# LPC1768_3.net
KiCad netlist of a schematic drawn in Altium Designer
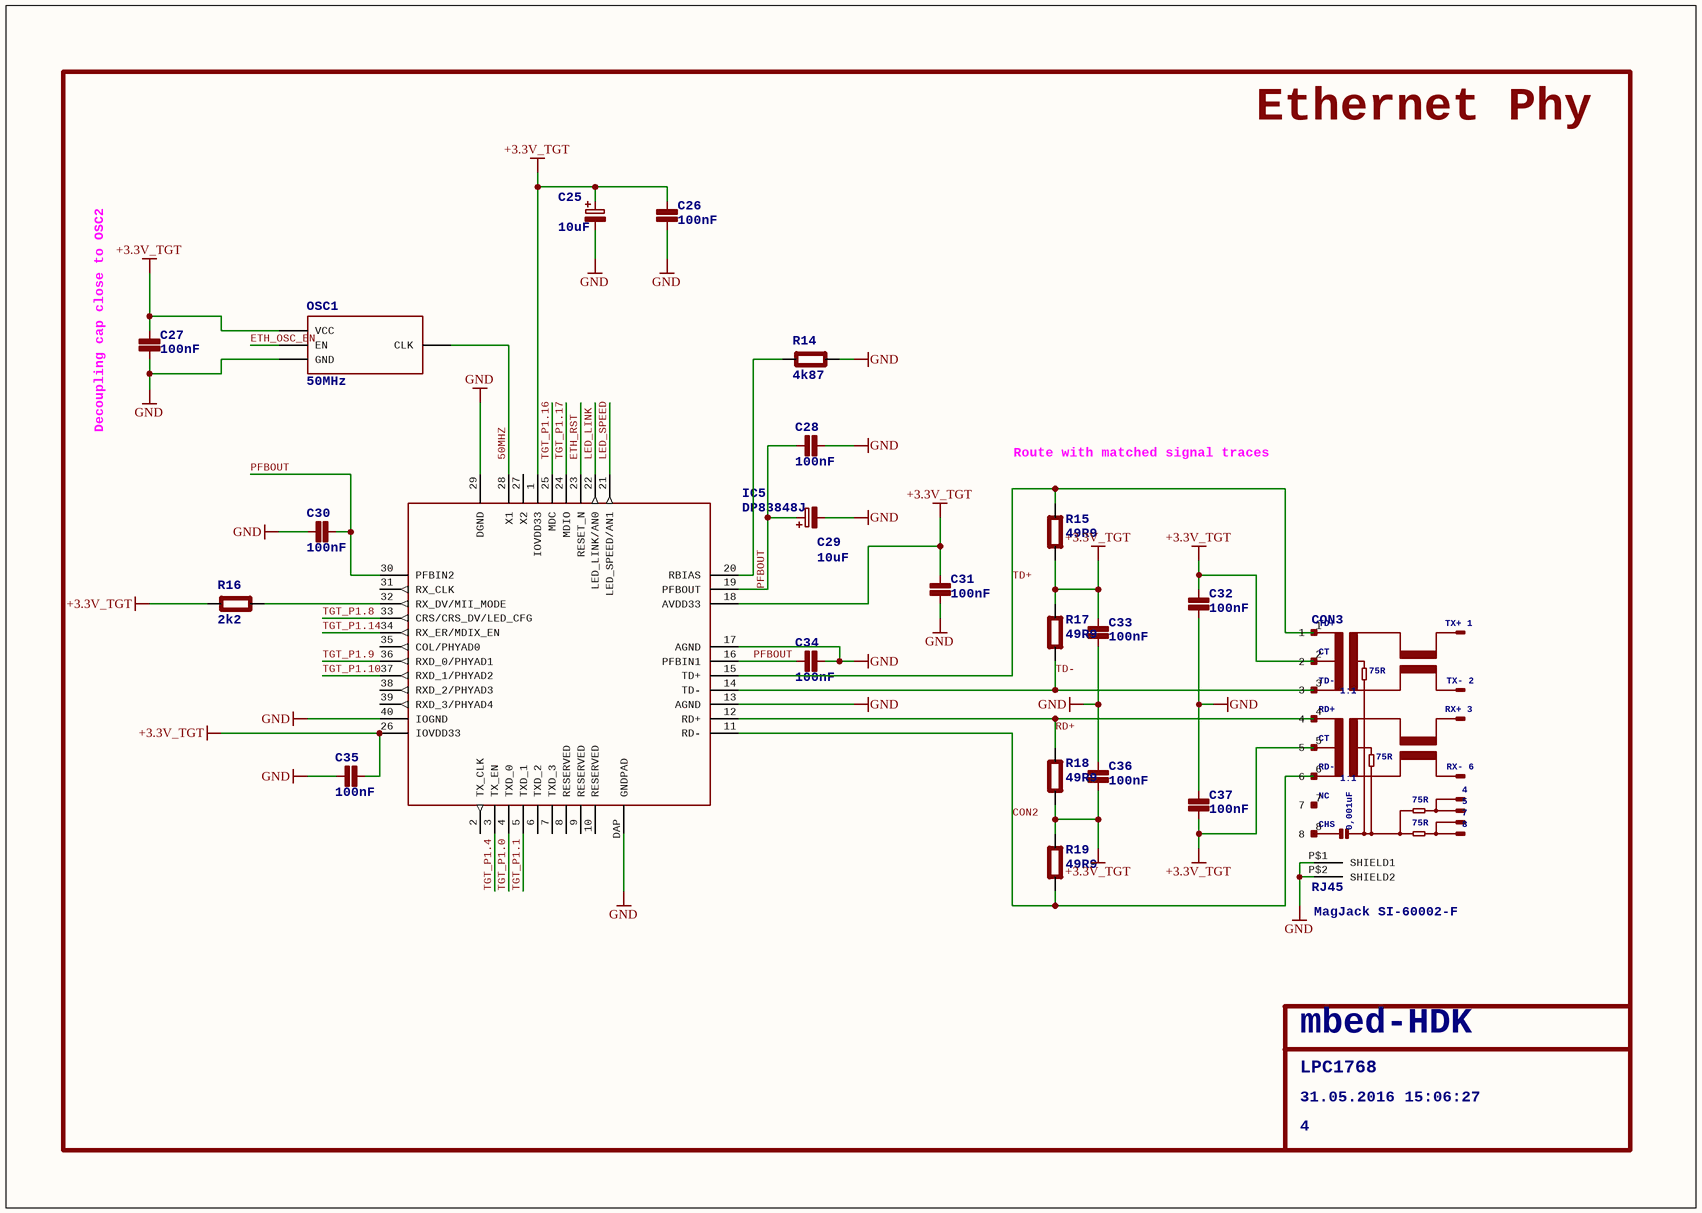
[diagram p0: LPC1768_3.SchDoc]

(export (version "E")
  (design (tool "Eeschema 10.0.6"))
  (components
    (comp (ref "C25") (value "10uF") (footprint "CASE-B") (libsource (lib "mbed-HDK") (part "C-POLB")))
    (comp (ref "C26") (value "100nF") (footprint "0603") (libsource (lib "mbed-HDK") (part "C0603")))
    (comp (ref "C27") (value "100nF") (footprint "0603") (libsource (lib "mbed-HDK") (part "C0603")))
    (comp (ref "C28") (value "100nF") (footprint "0603") (libsource (lib "") (part "C0603_1")))
    (comp (ref "C29") (value "10uF") (footprint "CASE-B") (libsource (lib "") (part "C-POLB_1")))
    (comp (ref "C30") (value "100nF") (footprint "0603") (libsource (lib "") (part "C0603_2")))
    (comp (ref "C31") (value "100nF") (footprint "0603") (libsource (lib "mbed-HDK") (part "C0603")))
    (comp (ref "C32") (value "100nF") (footprint "0603") (libsource (lib "mbed-HDK") (part "C0603")))
    (comp (ref "C33") (value "100nF") (footprint "0603") (libsource (lib "mbed-HDK") (part "C0603")))
    (comp (ref "C34") (value "100nF") (footprint "0603") (libsource (lib "") (part "C0603_2")))
    (comp (ref "C35") (value "100nF") (footprint "0603") (libsource (lib "") (part "C0603_1")))
    (comp (ref "C36") (value "100nF") (footprint "0603") (libsource (lib "mbed-HDK") (part "C0603")))
    (comp (ref "C37") (value "100nF") (footprint "0603") (libsource (lib "mbed-HDK") (part "C0603")))
    (comp (ref "CON3")
      (value "RJ45")
      (footprint "RJ45")
      (description "Magjack SI-68002")
      (fields
        (field (name "75R") "75R")
        (field (name "75R_1") "75R")
        (field (name "75R_2") "75R")
        (field (name "75R_3") "75R")
        (field (name "TD+") "TD+")
        (field (name "CT") "CT")
        (field (name "TD-") "TD-")
        (field (name "RD+") "RD+")
        (field (name "CT_1") "CT")
        (field (name "RD-") "RD-")
        (field (name "NC") "NC")
        (field (name "CHS") "CHS")
        (field (name "0,001UF") "0,001uF")
        (field (name "RX+3") "RX+ 3")
        (field (name "TX-2") "TX- 2")
        (field (name "TX+1") "TX+ 1")
        (field (name "RX-6") "RX- 6")
        (field (name "4") "4")
        (field (name "5") "5")
        (field (name "7") "7")
        (field (name "8") "8")
        (field (name "1:1") "1:1")
        (field (name "1:1_1") "1:1")
        (field (name "MAGJACKSI-60002-F") "MagJack SI-60002-F")
      )
      (libsource (lib "mbed-HDK") (part "RJ45"))
    )
    (comp (ref "IC5")
      (value "DP83848J")
      (footprint "LLP-40")
      (description "National Semiconductor DP83848J PHYTER Mini LS Single Port 10/100 Ethernet Transceiver")
      (libsource (lib "mbed-HDK") (part "DP83848J"))
    )
    (comp (ref "OSC1")
      (value "50MHz")
      (footprint "3.2X.2.5")
      (libsource (lib "mbed-HDK") (part "OSCILLATOR"))
    )
    (comp (ref "R14") (value "4k87") (footprint "0603") (libsource (lib "mbed-HDK") (part "R0603")))
    (comp (ref "R15") (value "49R9") (footprint "0603") (libsource (lib "mbed-HDK") (part "R0603")))
    (comp (ref "R16") (value "2k2") (footprint "0603") (libsource (lib "mbed-HDK") (part "R0603")))
    (comp (ref "R17") (value "49R9") (footprint "0603") (libsource (lib "mbed-HDK") (part "R0603")))
    (comp (ref "R18") (value "49R9") (footprint "0603") (libsource (lib "mbed-HDK") (part "R0603")))
    (comp (ref "R19") (value "49R9") (footprint "0603") (libsource (lib "mbed-HDK") (part "R0603")))
  )
  (nets
    (net (code "1") (name "+3.3V_TGT") (class "Default")
      (node (ref "C25") (pin "1") (pinfunction "1_1") (pintype "passive"))
      (node (ref "C26") (pin "1") (pinfunction "P$1_1") (pintype "passive"))
      (node (ref "C27") (pin "1") (pinfunction "P$1_1") (pintype "passive"))
      (node (ref "C31") (pin "1") (pinfunction "P$1_1") (pintype "passive"))
      (node (ref "C32") (pin "1") (pinfunction "P$1_1") (pintype "passive"))
      (node (ref "C33") (pin "1") (pinfunction "P$1_1") (pintype "passive"))
      (node (ref "C35") (pin "1") (pinfunction "P$1_1") (pintype "passive"))
      (node (ref "C36") (pin "2") (pinfunction "P$2_2") (pintype "passive"))
      (node (ref "C37") (pin "2") (pinfunction "P$2_2") (pintype "passive"))
      (node (ref "CON3") (pin "2") (pinfunction "2_2") (pintype "passive"))
      (node (ref "CON3") (pin "5") (pinfunction "5_5") (pintype "passive"))
      (node (ref "IC5") (pin "1") (pinfunction "IOVDD33_1") (pintype "power_in"))
      (node (ref "IC5") (pin "18") (pinfunction "AVDD33_18") (pintype "power_in"))
      (node (ref "IC5") (pin "26") (pinfunction "IOVDD33_26") (pintype "power_in"))
      (node (ref "OSC1") (pin "P$4") (pinfunction "VCC_P$4") (pintype "passive"))
      (node (ref "R15") (pin "1") (pinfunction "P$1_1") (pintype "passive"))
      (node (ref "R16") (pin "1") (pinfunction "P$1_1") (pintype "passive"))
      (node (ref "R17") (pin "2") (pinfunction "P$2_2") (pintype "passive"))
      (node (ref "R18") (pin "1") (pinfunction "P$1_1") (pintype "passive"))
      (node (ref "R19") (pin "2") (pinfunction "P$2_2") (pintype "passive"))
    )
    (net (code "2") (name "/50MHZ") (class "Default")
      (node (ref "IC5") (pin "28") (pinfunction "X1_28") (pintype "passive"))
      (node (ref "OSC1") (pin "P$3") (pinfunction "CLK_P$3") (pintype "passive"))
    )
    (net (code "3") (name "/CON2") (class "Default")
      (node (ref "CON3") (pin "6") (pinfunction "6_6") (pintype "passive"))
      (node (ref "IC5") (pin "11") (pinfunction "RD-_11") (pintype "passive"))
      (node (ref "R19") (pin "1") (pinfunction "P$1_1") (pintype "passive"))
    )
    (net (code "4") (name "/ETH_OSC_EN") (class "Default")
      (node (ref "OSC1") (pin "P$1") (pinfunction "EN_P$1") (pintype "passive"))
    )
    (net (code "5") (name "/ETH_RST") (class "Default")
      (node (ref "IC5") (pin "23") (pinfunction "RESET_N_23") (pintype "passive"))
    )
    (net (code "6") (name "/LED_LINK") (class "Default")
      (node (ref "IC5") (pin "22") (pinfunction "LED_LINK/AN0_22") (pintype "output"))
    )
    (net (code "7") (name "/LED_SPEED") (class "Default")
      (node (ref "IC5") (pin "21") (pinfunction "LED_SPEED/AN1_21") (pintype "output"))
    )
    (net (code "8") (name "/PFBOUT") (class "Default")
      (node (ref "C28") (pin "2") (pinfunction "P$2_2") (pintype "passive"))
      (node (ref "C29") (pin "1") (pinfunction "1_1") (pintype "passive"))
      (node (ref "C30") (pin "2") (pinfunction "P$2_2") (pintype "passive"))
      (node (ref "C34") (pin "1") (pinfunction "P$1_1") (pintype "passive"))
      (node (ref "IC5") (pin "16") (pinfunction "PFBIN1_16") (pintype "passive"))
      (node (ref "IC5") (pin "19") (pinfunction "PFBOUT_19") (pintype "passive"))
      (node (ref "IC5") (pin "30") (pinfunction "PFBIN2_30") (pintype "passive"))
    )
    (net (code "9") (name "/RD+") (class "Default")
      (node (ref "CON3") (pin "4") (pinfunction "4_4") (pintype "passive"))
      (node (ref "IC5") (pin "12") (pinfunction "RD+_12") (pintype "passive"))
      (node (ref "R18") (pin "2") (pinfunction "P$2_2") (pintype "passive"))
    )
    (net (code "10") (name "/TD+") (class "Default")
      (node (ref "CON3") (pin "1") (pinfunction "1_1") (pintype "passive"))
      (node (ref "IC5") (pin "15") (pinfunction "TD+_15") (pintype "passive"))
      (node (ref "R15") (pin "2") (pinfunction "P$2_2") (pintype "passive"))
    )
    (net (code "11") (name "/TD-") (class "Default")
      (node (ref "CON3") (pin "3") (pinfunction "3_3") (pintype "passive"))
      (node (ref "IC5") (pin "14") (pinfunction "TD-_14") (pintype "passive"))
      (node (ref "R17") (pin "1") (pinfunction "P$1_1") (pintype "passive"))
    )
    (net (code "12") (name "/TGT_P1.0") (class "Default")
      (node (ref "IC5") (pin "4") (pinfunction "TXD_0_4") (pintype "passive"))
    )
    (net (code "13") (name "/TGT_P1.1") (class "Default")
      (node (ref "IC5") (pin "5") (pinfunction "TXD_1_5") (pintype "passive"))
    )
    (net (code "14") (name "/TGT_P1.4") (class "Default")
      (node (ref "IC5") (pin "3") (pinfunction "TX_EN_3") (pintype "passive"))
    )
    (net (code "15") (name "/TGT_P1.8") (class "Default")
      (node (ref "IC5") (pin "33") (pinfunction "CRS/CRS_DV/LED_CFG_33") (pintype "output"))
    )
    (net (code "16") (name "/TGT_P1.9") (class "Default")
      (node (ref "IC5") (pin "36") (pinfunction "RXD_0/PHYAD1_36") (pintype "output"))
    )
    (net (code "17") (name "/TGT_P1.10") (class "Default")
      (node (ref "IC5") (pin "37") (pinfunction "RXD_1/PHYAD2_37") (pintype "output"))
    )
    (net (code "18") (name "/TGT_P1.14") (class "Default")
      (node (ref "IC5") (pin "34") (pinfunction "RX_ER/MDIX_EN_34") (pintype "output"))
    )
    (net (code "19") (name "/TGT_P1.16") (class "Default")
      (node (ref "IC5") (pin "25") (pinfunction "MDC_25") (pintype "passive"))
    )
    (net (code "20") (name "/TGT_P1.17") (class "Default")
      (node (ref "IC5") (pin "24") (pinfunction "MDIO_24") (pintype "passive"))
    )
    (net (code "21") (name "GND") (class "Default")
      (node (ref "C25") (pin "2") (pinfunction "2_2") (pintype "passive"))
      (node (ref "C26") (pin "2") (pinfunction "P$2_2") (pintype "passive"))
      (node (ref "C27") (pin "2") (pinfunction "P$2_2") (pintype "passive"))
      (node (ref "C28") (pin "1") (pinfunction "P$1_1") (pintype "passive"))
      (node (ref "C29") (pin "2") (pinfunction "2_2") (pintype "passive"))
      (node (ref "C30") (pin "1") (pinfunction "P$1_1") (pintype "passive"))
      (node (ref "C31") (pin "2") (pinfunction "P$2_2") (pintype "passive"))
      (node (ref "C32") (pin "2") (pinfunction "P$2_2") (pintype "passive"))
      (node (ref "C33") (pin "2") (pinfunction "P$2_2") (pintype "passive"))
      (node (ref "C34") (pin "2") (pinfunction "P$2_2") (pintype "passive"))
      (node (ref "C35") (pin "2") (pinfunction "P$2_2") (pintype "passive"))
      (node (ref "C36") (pin "1") (pinfunction "P$1_1") (pintype "passive"))
      (node (ref "C37") (pin "1") (pinfunction "P$1_1") (pintype "passive"))
      (node (ref "CON3") (pin "P$1") (pinfunction "SHIELD1_P$1") (pintype "passive"))
      (node (ref "CON3") (pin "P$2") (pinfunction "SHIELD2_P$2") (pintype "passive"))
      (node (ref "IC5") (pin "13") (pinfunction "AGND_13") (pintype "power_in"))
      (node (ref "IC5") (pin "17") (pinfunction "AGND_17") (pintype "power_in"))
      (node (ref "IC5") (pin "29") (pinfunction "DGND_29") (pintype "power_in"))
      (node (ref "IC5") (pin "40") (pinfunction "IOGND_40") (pintype "power_in"))
      (node (ref "IC5") (pin "DAP") (pinfunction "GNDPAD_DAP") (pintype "power_in"))
      (node (ref "OSC1") (pin "P$2") (pinfunction "GND_P$2") (pintype "passive"))
      (node (ref "R14") (pin "1") (pinfunction "P$1_1") (pintype "passive"))
    )
    (net (code "22") (name "Net-(IC5-RBIAS)") (class "Default")
      (node (ref "IC5") (pin "20") (pinfunction "RBIAS_20") (pintype "passive"))
      (node (ref "R14") (pin "2") (pinfunction "P$2_2") (pintype "passive"))
    )
    (net (code "23") (name "Net-(IC5-RX_DV{slash}MII_MODE)") (class "Default")
      (node (ref "IC5") (pin "32") (pinfunction "RX_DV/MII_MODE_32") (pintype "output"))
      (node (ref "R16") (pin "2") (pinfunction "P$2_2") (pintype "passive"))
    )
    (net (code "24") (name "unconnected-(CON3-Pad7)") (class "Default")
      (node (ref "CON3") (pin "7") (pinfunction "7_7") (pintype "passive"))
    )
    (net (code "25") (name "unconnected-(CON3-Pad8)") (class "Default")
      (node (ref "CON3") (pin "8") (pinfunction "8_8") (pintype "passive"))
    )
    (net (code "26") (name "unconnected-(IC5-COL{slash}PHYAD0-Pad35)") (class "Default")
      (node (ref "IC5") (pin "35") (pinfunction "COL/PHYAD0_35") (pintype "output"))
    )
    (net (code "27") (name "unconnected-(IC5-RESERVED-Pad8)") (class "Default")
      (node (ref "IC5") (pin "8") (pinfunction "RESERVED_8") (pintype "passive"))
    )
    (net (code "28") (name "unconnected-(IC5-RESERVED-Pad9)") (class "Default")
      (node (ref "IC5") (pin "9") (pinfunction "RESERVED_9") (pintype "passive"))
    )
    (net (code "29") (name "unconnected-(IC5-RESERVED-Pad10)") (class "Default")
      (node (ref "IC5") (pin "10") (pinfunction "RESERVED_10") (pintype "passive"))
    )
    (net (code "30") (name "unconnected-(IC5-RXD_2{slash}PHYAD3-Pad38)") (class "Default")
      (node (ref "IC5") (pin "38") (pinfunction "RXD_2/PHYAD3_38") (pintype "output"))
    )
    (net (code "31") (name "unconnected-(IC5-RXD_3{slash}PHYAD4-Pad39)") (class "Default")
      (node (ref "IC5") (pin "39") (pinfunction "RXD_3/PHYAD4_39") (pintype "output"))
    )
    (net (code "32") (name "unconnected-(IC5-RX_CLK-Pad31)") (class "Default")
      (node (ref "IC5") (pin "31") (pinfunction "RX_CLK_31") (pintype "output"))
    )
    (net (code "33") (name "unconnected-(IC5-TXD_2-Pad6)") (class "Default")
      (node (ref "IC5") (pin "6") (pinfunction "TXD_2_6") (pintype "passive"))
    )
    (net (code "34") (name "unconnected-(IC5-TXD_3-Pad7)") (class "Default")
      (node (ref "IC5") (pin "7") (pinfunction "TXD_3_7") (pintype "passive"))
    )
    (net (code "35") (name "unconnected-(IC5-TX_CLK-Pad2)") (class "Default")
      (node (ref "IC5") (pin "2") (pinfunction "TX_CLK_2") (pintype "output"))
    )
    (net (code "36") (name "unconnected-(IC5-X2-Pad27)") (class "Default")
      (node (ref "IC5") (pin "27") (pinfunction "X2_27") (pintype "passive"))
    )
  )
)
